# HIVE_SIGHT_NUCLEO.net
KiCad netlist of a schematic drawn in Altium Designer
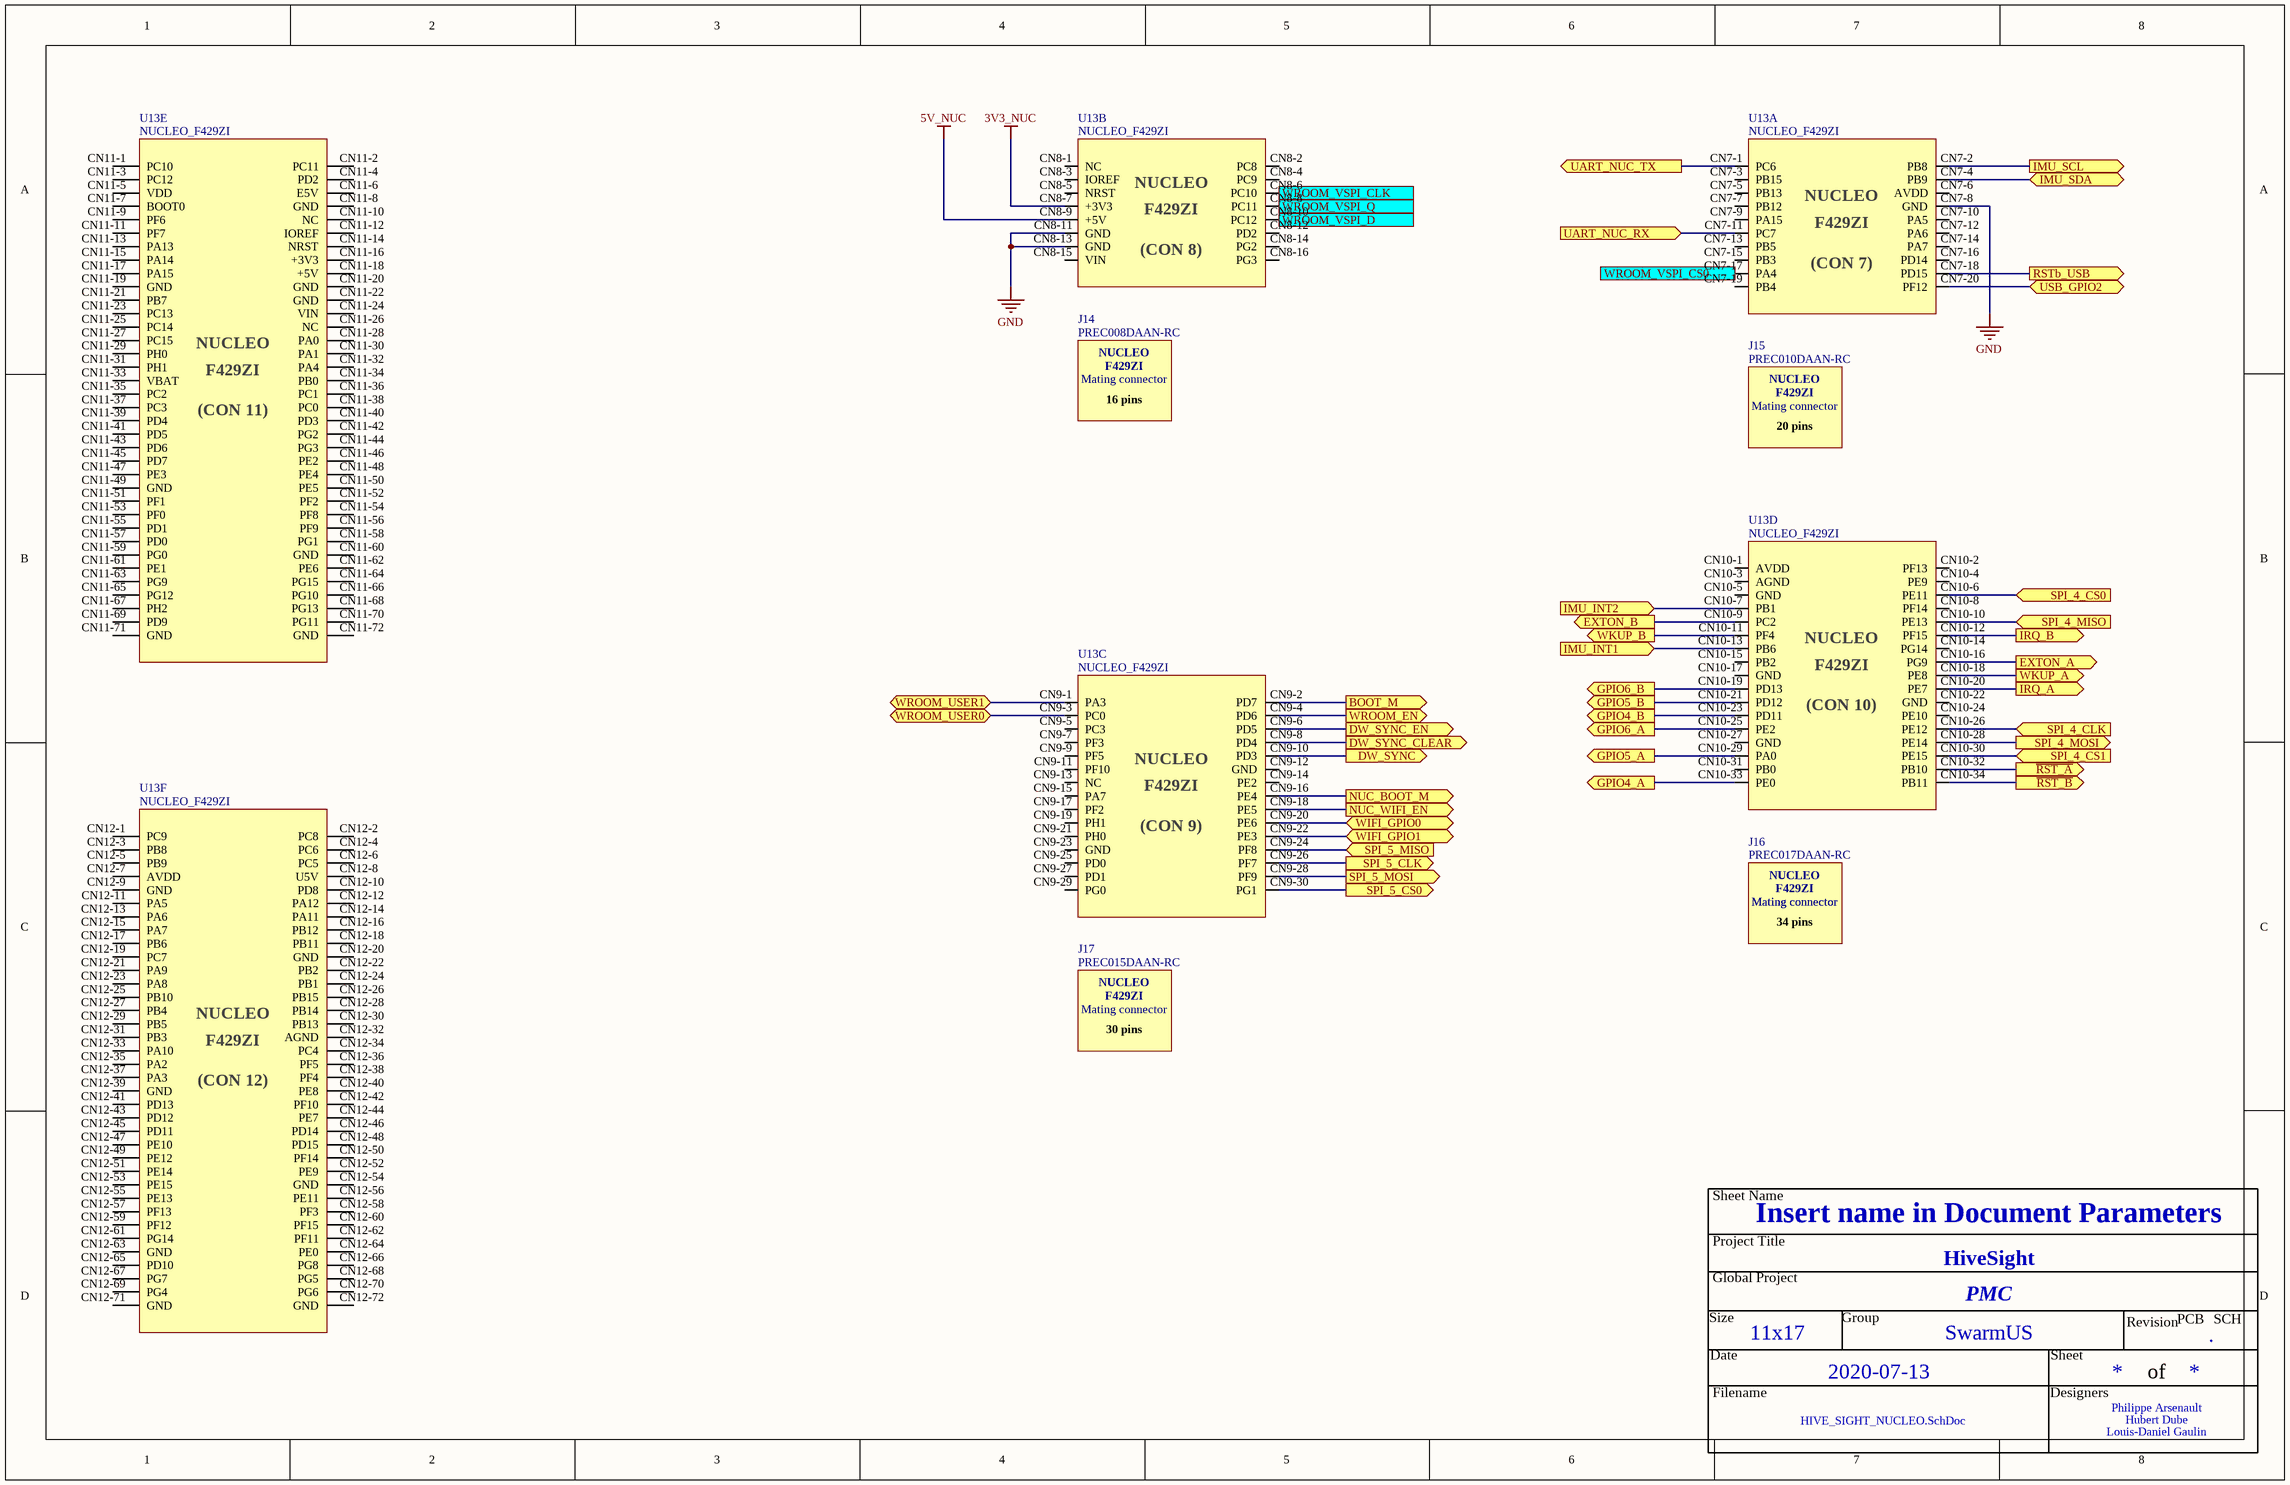
[diagram p0: HIVE_SIGHT_NUCLEO.SchDoc]

(export (version "E")
  (design (tool "Eeschema 10.0.6"))
  (components
    (comp (ref "J14")
      (value "PREC008DAAN-RC")
      (footprint "CON_HDR_NUCLEO_F429ZI_C008DAAN-RC")
      (description "CON - Header 16 positions 2x8  0.100\" - TH")
      (fields (field (name "CREATEDBY/DATE") "Louis-Daniel Gaulin / 21-10-2020"))
      (libsource (lib "SWARMUS_LIB") (part "CON_HDR_NUCLEO_F429ZI_PREC008DAAN-RC"))
    )
    (comp (ref "J15")
      (value "PREC010DAAN-RC")
      (footprint "CON_HDR_NUCLEO_F429ZI_C010DAAN-RC")
      (description "CON - Header 20 positions 2x10  0.100\" - TH")
      (fields (field (name "CREATEDBY/DATE") "Louis-Daniel Gaulin / 21-10-2020"))
      (libsource (lib "SWARMUS_LIB") (part "CON_HDR_NUCLEO_F429ZI_PREC010DAAN-RC"))
    )
    (comp (ref "J16")
      (value "PREC017DAAN-RC")
      (footprint "CON_HDR_NUCLEO_F429ZI_C017DAAN-RC")
      (description "CON - Header 34 positions 2x17  0.100\" - TH")
      (fields (field (name "CREATEDBY/DATE") "Louis-Daniel Gaulin / 21-10-2020"))
      (libsource (lib "SWARMUS_LIB") (part "CON_HDR_NUCLEO_F429ZI_PREC017DAAN-RC"))
    )
    (comp (ref "J17")
      (value "PREC015DAAN-RC")
      (footprint "CON_HDR_NUCLEO_F429ZI_C015DAAN-RC")
      (description "CON - Header 30 positions 2x15  0.100\" - TH")
      (fields (field (name "CREATEDBY/DATE") "Louis-Daniel Gaulin / 21-10-2020"))
      (libsource (lib "SWARMUS_LIB") (part "CON_HDR_NUCLEO_F429ZI_PREC015DAAN-RC"))
    )
    (comp (ref "U13")
      (value "NUCLEO_F429ZI")
      (footprint "MOD_NUCLEO-F429ZI")
      (description "MOD - F429ZI MCU Nucleo development board - MOD")
      (fields (field (name "CREATEDBY/DATE") "Louis-Daniel Gaulin"))
      (libsource (lib "SWARMUS_LIB") (part "MOD_NUCLEO_F429ZI"))
    )
  )
  (nets
    (net (code "1") (name "/BOOT_M") (class "Default")
      (node (ref "U13") (pin "CN9-2") (pinfunction "PD7_CN9-2") (pintype "passive"))
    )
    (net (code "2") (name "/DW_SYNC") (class "Default")
      (node (ref "U13") (pin "CN9-10") (pinfunction "PD3_CN9-10") (pintype "passive"))
    )
    (net (code "3") (name "/DW_SYNC_CLEAR") (class "Default")
      (node (ref "U13") (pin "CN9-8") (pinfunction "PD4_CN9-8") (pintype "passive"))
    )
    (net (code "4") (name "/DW_SYNC_EN") (class "Default")
      (node (ref "U13") (pin "CN9-6") (pinfunction "PD5_CN9-6") (pintype "passive"))
    )
    (net (code "5") (name "/EXTON_A") (class "Default")
      (node (ref "U13") (pin "CN10-16") (pinfunction "PG9_CN10-16") (pintype "passive"))
    )
    (net (code "6") (name "/EXTON_B") (class "Default")
      (node (ref "U13") (pin "CN10-9") (pinfunction "PC2_CN10-9") (pintype "passive"))
    )
    (net (code "7") (name "/GPIO4_A") (class "Default")
      (node (ref "U13") (pin "CN10-33") (pinfunction "PE0_CN10-33") (pintype "passive"))
    )
    (net (code "8") (name "/GPIO4_B") (class "Default")
      (node (ref "U13") (pin "CN10-23") (pinfunction "PD11_CN10-23") (pintype "passive"))
    )
    (net (code "9") (name "/GPIO5_A") (class "Default")
      (node (ref "U13") (pin "CN10-29") (pinfunction "PA0_CN10-29") (pintype "passive"))
    )
    (net (code "10") (name "/GPIO5_B") (class "Default")
      (node (ref "U13") (pin "CN10-21") (pinfunction "PD12_CN10-21") (pintype "passive"))
    )
    (net (code "11") (name "/GPIO6_A") (class "Default")
      (node (ref "U13") (pin "CN10-25") (pinfunction "PE2_CN10-25") (pintype "passive"))
    )
    (net (code "12") (name "/GPIO6_B") (class "Default")
      (node (ref "U13") (pin "CN10-19") (pinfunction "PD13_CN10-19") (pintype "passive"))
    )
    (net (code "13") (name "/IMU_INT1") (class "Default")
      (node (ref "U13") (pin "CN10-13") (pinfunction "PB6_CN10-13") (pintype "passive"))
    )
    (net (code "14") (name "/IMU_INT2") (class "Default")
      (node (ref "U13") (pin "CN10-7") (pinfunction "PB1_CN10-7") (pintype "passive"))
    )
    (net (code "15") (name "/IMU_SCL") (class "Default")
      (node (ref "U13") (pin "CN7-2") (pinfunction "PB8_CN7-2") (pintype "passive"))
    )
    (net (code "16") (name "/IMU_SDA") (class "Default")
      (node (ref "U13") (pin "CN7-4") (pinfunction "PB9_CN7-4") (pintype "passive"))
    )
    (net (code "17") (name "/IRQ_A") (class "Default")
      (node (ref "U13") (pin "CN10-20") (pinfunction "PE7_CN10-20") (pintype "passive"))
    )
    (net (code "18") (name "/IRQ_B") (class "Default")
      (node (ref "U13") (pin "CN10-12") (pinfunction "PF15_CN10-12") (pintype "passive"))
    )
    (net (code "19") (name "/NUC_BOOT_M") (class "Default")
      (node (ref "U13") (pin "CN9-16") (pinfunction "PE4_CN9-16") (pintype "passive"))
    )
    (net (code "20") (name "/NUC_WIFI_EN") (class "Default")
      (node (ref "U13") (pin "CN9-18") (pinfunction "PE5_CN9-18") (pintype "passive"))
    )
    (net (code "21") (name "/RST_A") (class "Default")
      (node (ref "U13") (pin "CN10-32") (pinfunction "PB10_CN10-32") (pintype "passive"))
    )
    (net (code "22") (name "/RST_B") (class "Default")
      (node (ref "U13") (pin "CN10-34") (pinfunction "PB11_CN10-34") (pintype "passive"))
    )
    (net (code "23") (name "/RSTb_USB") (class "Default")
      (node (ref "U13") (pin "CN7-18") (pinfunction "PD15_CN7-18") (pintype "passive"))
    )
    (net (code "24") (name "/SPI_4_CLK") (class "Default")
      (node (ref "U13") (pin "CN10-26") (pinfunction "PE12_CN10-26") (pintype "passive"))
    )
    (net (code "25") (name "/SPI_4_CS0") (class "Default")
      (node (ref "U13") (pin "CN10-6") (pinfunction "PE11_CN10-6") (pintype "passive"))
    )
    (net (code "26") (name "/SPI_4_CS1") (class "Default")
      (node (ref "U13") (pin "CN10-30") (pinfunction "PE15_CN10-30") (pintype "passive"))
    )
    (net (code "27") (name "/SPI_4_MISO") (class "Default")
      (node (ref "U13") (pin "CN10-10") (pinfunction "PE13_CN10-10") (pintype "passive"))
    )
    (net (code "28") (name "/SPI_4_MOSI") (class "Default")
      (node (ref "U13") (pin "CN10-28") (pinfunction "PE14_CN10-28") (pintype "passive"))
    )
    (net (code "29") (name "/SPI_5_CLK") (class "Default")
      (node (ref "U13") (pin "CN9-26") (pinfunction "PF7_CN9-26") (pintype "passive"))
    )
    (net (code "30") (name "/SPI_5_CS0") (class "Default")
      (node (ref "U13") (pin "CN9-30") (pinfunction "PG1_CN9-30") (pintype "passive"))
    )
    (net (code "31") (name "/SPI_5_MISO") (class "Default")
      (node (ref "U13") (pin "CN9-24") (pinfunction "PF8_CN9-24") (pintype "passive"))
    )
    (net (code "32") (name "/SPI_5_MOSI") (class "Default")
      (node (ref "U13") (pin "CN9-28") (pinfunction "PF9_CN9-28") (pintype "passive"))
    )
    (net (code "33") (name "/UART_NUC_RX") (class "Default")
      (node (ref "U13") (pin "CN7-11") (pinfunction "PC7_CN7-11") (pintype "passive"))
    )
    (net (code "34") (name "/UART_NUC_TX") (class "Default")
      (node (ref "U13") (pin "CN7-1") (pinfunction "PC6_CN7-1") (pintype "passive"))
    )
    (net (code "35") (name "/USB_GPIO2") (class "Default")
      (node (ref "U13") (pin "CN7-20") (pinfunction "PF12_CN7-20") (pintype "passive"))
    )
    (net (code "36") (name "/WIFI_GPIO0") (class "Default")
      (node (ref "U13") (pin "CN9-20") (pinfunction "PE6_CN9-20") (pintype "passive"))
    )
    (net (code "37") (name "/WIFI_GPIO1") (class "Default")
      (node (ref "U13") (pin "CN9-22") (pinfunction "PE3_CN9-22") (pintype "passive"))
    )
    (net (code "38") (name "/WKUP_A") (class "Default")
      (node (ref "U13") (pin "CN10-18") (pinfunction "PE8_CN10-18") (pintype "passive"))
    )
    (net (code "39") (name "/WKUP_B") (class "Default")
      (node (ref "U13") (pin "CN10-11") (pinfunction "PF4_CN10-11") (pintype "passive"))
    )
    (net (code "40") (name "/WROOM_EN") (class "Default")
      (node (ref "U13") (pin "CN9-4") (pinfunction "PD6_CN9-4") (pintype "passive"))
    )
    (net (code "41") (name "/WROOM_USER0") (class "Default")
      (node (ref "U13") (pin "CN9-3") (pinfunction "PC0_CN9-3") (pintype "passive"))
    )
    (net (code "42") (name "/WROOM_USER1") (class "Default")
      (node (ref "U13") (pin "CN9-1") (pinfunction "PA3_CN9-1") (pintype "passive"))
    )
    (net (code "43") (name "/WROOM_VSPI_CLK") (class "Default")
      (node (ref "U13") (pin "CN8-6") (pinfunction "PC10_CN8-6") (pintype "passive"))
    )
    (net (code "44") (name "/WROOM_VSPI_CS0") (class "Default")
      (node (ref "U13") (pin "CN7-17") (pinfunction "PA4_CN7-17") (pintype "passive"))
    )
    (net (code "45") (name "/WROOM_VSPI_D") (class "Default")
      (node (ref "U13") (pin "CN8-10") (pinfunction "PC12_CN8-10") (pintype "passive"))
    )
    (net (code "46") (name "/WROOM_VSPI_Q") (class "Default")
      (node (ref "U13") (pin "CN8-8") (pinfunction "PC11_CN8-8") (pintype "passive"))
    )
    (net (code "47") (name "3V3_NUC") (class "Default")
      (node (ref "U13") (pin "CN8-7") (pinfunction "+3V3_CN8-7") (pintype "passive"))
    )
    (net (code "48") (name "5V_NUC") (class "Default")
      (node (ref "U13") (pin "CN8-9") (pinfunction "+5V_CN8-9") (pintype "passive"))
    )
    (net (code "49") (name "GND") (class "Default")
      (node (ref "U13") (pin "CN7-8") (pinfunction "GND_CN7-8") (pintype "passive"))
      (node (ref "U13") (pin "CN8-11") (pinfunction "GND_CN8-11") (pintype "passive"))
      (node (ref "U13") (pin "CN8-13") (pinfunction "GND_CN8-13") (pintype "passive"))
    )
    (net (code "50") (name "unconnected-(U13A-AVDD-PadCN7-6)") (class "Default")
      (node (ref "U13") (pin "CN7-6") (pinfunction "AVDD_CN7-6") (pintype "passive"))
    )
    (net (code "51") (name "unconnected-(U13A-PA5-PadCN7-10)") (class "Default")
      (node (ref "U13") (pin "CN7-10") (pinfunction "PA5_CN7-10") (pintype "passive"))
    )
    (net (code "52") (name "unconnected-(U13A-PA6-PadCN7-12)") (class "Default")
      (node (ref "U13") (pin "CN7-12") (pinfunction "PA6_CN7-12") (pintype "passive"))
    )
    (net (code "53") (name "unconnected-(U13A-PA7-PadCN7-14)") (class "Default")
      (node (ref "U13") (pin "CN7-14") (pinfunction "PA7_CN7-14") (pintype "passive"))
    )
    (net (code "54") (name "unconnected-(U13A-PA15-PadCN7-9)") (class "Default")
      (node (ref "U13") (pin "CN7-9") (pinfunction "PA15_CN7-9") (pintype "passive"))
    )
    (net (code "55") (name "unconnected-(U13A-PB3-PadCN7-15)") (class "Default")
      (node (ref "U13") (pin "CN7-15") (pinfunction "PB3_CN7-15") (pintype "passive"))
    )
    (net (code "56") (name "unconnected-(U13A-PB4-PadCN7-19)") (class "Default")
      (node (ref "U13") (pin "CN7-19") (pinfunction "PB4_CN7-19") (pintype "passive"))
    )
    (net (code "57") (name "unconnected-(U13A-PB5-PadCN7-13)") (class "Default")
      (node (ref "U13") (pin "CN7-13") (pinfunction "PB5_CN7-13") (pintype "passive"))
    )
    (net (code "58") (name "unconnected-(U13A-PB12-PadCN7-7)") (class "Default")
      (node (ref "U13") (pin "CN7-7") (pinfunction "PB12_CN7-7") (pintype "passive"))
    )
    (net (code "59") (name "unconnected-(U13A-PB13-PadCN7-5)") (class "Default")
      (node (ref "U13") (pin "CN7-5") (pinfunction "PB13_CN7-5") (pintype "passive"))
    )
    (net (code "60") (name "unconnected-(U13A-PB15-PadCN7-3)") (class "Default")
      (node (ref "U13") (pin "CN7-3") (pinfunction "PB15_CN7-3") (pintype "passive"))
    )
    (net (code "61") (name "unconnected-(U13A-PD14-PadCN7-16)") (class "Default")
      (node (ref "U13") (pin "CN7-16") (pinfunction "PD14_CN7-16") (pintype "passive"))
    )
    (net (code "62") (name "unconnected-(U13B-IOREF-PadCN8-3)") (class "Default")
      (node (ref "U13") (pin "CN8-3") (pinfunction "IOREF_CN8-3") (pintype "passive"))
    )
    (net (code "63") (name "unconnected-(U13B-NC-PadCN8-1)") (class "Default")
      (node (ref "U13") (pin "CN8-1") (pinfunction "NC_CN8-1") (pintype "passive"))
    )
    (net (code "64") (name "unconnected-(U13B-NRST-PadCN8-5)") (class "Default")
      (node (ref "U13") (pin "CN8-5") (pinfunction "NRST_CN8-5") (pintype "passive"))
    )
    (net (code "65") (name "unconnected-(U13B-PC8-PadCN8-2)") (class "Default")
      (node (ref "U13") (pin "CN8-2") (pinfunction "PC8_CN8-2") (pintype "passive"))
    )
    (net (code "66") (name "unconnected-(U13B-PC9-PadCN8-4)") (class "Default")
      (node (ref "U13") (pin "CN8-4") (pinfunction "PC9_CN8-4") (pintype "passive"))
    )
    (net (code "67") (name "unconnected-(U13B-PD2-PadCN8-12)") (class "Default")
      (node (ref "U13") (pin "CN8-12") (pinfunction "PD2_CN8-12") (pintype "passive"))
    )
    (net (code "68") (name "unconnected-(U13B-PG2-PadCN8-14)") (class "Default")
      (node (ref "U13") (pin "CN8-14") (pinfunction "PG2_CN8-14") (pintype "passive"))
    )
    (net (code "69") (name "unconnected-(U13B-PG3-PadCN8-16)") (class "Default")
      (node (ref "U13") (pin "CN8-16") (pinfunction "PG3_CN8-16") (pintype "passive"))
    )
    (net (code "70") (name "unconnected-(U13B-VIN-PadCN8-15)") (class "Default")
      (node (ref "U13") (pin "CN8-15") (pinfunction "VIN_CN8-15") (pintype "passive"))
    )
    (net (code "71") (name "unconnected-(U13C-GND-PadCN9-12)") (class "Default")
      (node (ref "U13") (pin "CN9-12") (pinfunction "GND_CN9-12") (pintype "passive"))
    )
    (net (code "72") (name "unconnected-(U13C-GND-PadCN9-23)") (class "Default")
      (node (ref "U13") (pin "CN9-23") (pinfunction "GND_CN9-23") (pintype "passive"))
    )
    (net (code "73") (name "unconnected-(U13C-NC-PadCN9-13)") (class "Default")
      (node (ref "U13") (pin "CN9-13") (pinfunction "NC_CN9-13") (pintype "passive"))
    )
    (net (code "74") (name "unconnected-(U13C-PA7-PadCN9-15)") (class "Default")
      (node (ref "U13") (pin "CN9-15") (pinfunction "PA7_CN9-15") (pintype "passive"))
    )
    (net (code "75") (name "unconnected-(U13C-PC3-PadCN9-5)") (class "Default")
      (node (ref "U13") (pin "CN9-5") (pinfunction "PC3_CN9-5") (pintype "passive"))
    )
    (net (code "76") (name "unconnected-(U13C-PD0-PadCN9-25)") (class "Default")
      (node (ref "U13") (pin "CN9-25") (pinfunction "PD0_CN9-25") (pintype "passive"))
    )
    (net (code "77") (name "unconnected-(U13C-PD1-PadCN9-27)") (class "Default")
      (node (ref "U13") (pin "CN9-27") (pinfunction "PD1_CN9-27") (pintype "passive"))
    )
    (net (code "78") (name "unconnected-(U13C-PE2-PadCN9-14)") (class "Default")
      (node (ref "U13") (pin "CN9-14") (pinfunction "PE2_CN9-14") (pintype "passive"))
    )
    (net (code "79") (name "unconnected-(U13C-PF2-PadCN9-17)") (class "Default")
      (node (ref "U13") (pin "CN9-17") (pinfunction "PF2_CN9-17") (pintype "passive"))
    )
    (net (code "80") (name "unconnected-(U13C-PF3-PadCN9-7)") (class "Default")
      (node (ref "U13") (pin "CN9-7") (pinfunction "PF3_CN9-7") (pintype "passive"))
    )
    (net (code "81") (name "unconnected-(U13C-PF5-PadCN9-9)") (class "Default")
      (node (ref "U13") (pin "CN9-9") (pinfunction "PF5_CN9-9") (pintype "passive"))
    )
    (net (code "82") (name "unconnected-(U13C-PF10-PadCN9-11)") (class "Default")
      (node (ref "U13") (pin "CN9-11") (pinfunction "PF10_CN9-11") (pintype "passive"))
    )
    (net (code "83") (name "unconnected-(U13C-PG0-PadCN9-29)") (class "Default")
      (node (ref "U13") (pin "CN9-29") (pinfunction "PG0_CN9-29") (pintype "passive"))
    )
    (net (code "84") (name "unconnected-(U13C-PH0-PadCN9-21)") (class "Default")
      (node (ref "U13") (pin "CN9-21") (pinfunction "PH0_CN9-21") (pintype "passive"))
    )
    (net (code "85") (name "unconnected-(U13C-PH1-PadCN9-19)") (class "Default")
      (node (ref "U13") (pin "CN9-19") (pinfunction "PH1_CN9-19") (pintype "passive"))
    )
    (net (code "86") (name "unconnected-(U13D-AGND-PadCN10-3)") (class "Default")
      (node (ref "U13") (pin "CN10-3") (pinfunction "AGND_CN10-3") (pintype "passive"))
    )
    (net (code "87") (name "unconnected-(U13D-AVDD-PadCN10-1)") (class "Default")
      (node (ref "U13") (pin "CN10-1") (pinfunction "AVDD_CN10-1") (pintype "passive"))
    )
    (net (code "88") (name "unconnected-(U13D-GND-PadCN10-5)") (class "Default")
      (node (ref "U13") (pin "CN10-5") (pinfunction "GND_CN10-5") (pintype "passive"))
    )
    (net (code "89") (name "unconnected-(U13D-GND-PadCN10-17)") (class "Default")
      (node (ref "U13") (pin "CN10-17") (pinfunction "GND_CN10-17") (pintype "passive"))
    )
    (net (code "90") (name "unconnected-(U13D-GND-PadCN10-22)") (class "Default")
      (node (ref "U13") (pin "CN10-22") (pinfunction "GND_CN10-22") (pintype "passive"))
    )
    (net (code "91") (name "unconnected-(U13D-GND-PadCN10-27)") (class "Default")
      (node (ref "U13") (pin "CN10-27") (pinfunction "GND_CN10-27") (pintype "passive"))
    )
    (net (code "92") (name "unconnected-(U13D-PB0-PadCN10-31)") (class "Default")
      (node (ref "U13") (pin "CN10-31") (pinfunction "PB0_CN10-31") (pintype "passive"))
    )
    (net (code "93") (name "unconnected-(U13D-PB2-PadCN10-15)") (class "Default")
      (node (ref "U13") (pin "CN10-15") (pinfunction "PB2_CN10-15") (pintype "passive"))
    )
    (net (code "94") (name "unconnected-(U13D-PE9-PadCN10-4)") (class "Default")
      (node (ref "U13") (pin "CN10-4") (pinfunction "PE9_CN10-4") (pintype "passive"))
    )
    (net (code "95") (name "unconnected-(U13D-PE10-PadCN10-24)") (class "Default")
      (node (ref "U13") (pin "CN10-24") (pinfunction "PE10_CN10-24") (pintype "passive"))
    )
    (net (code "96") (name "unconnected-(U13D-PF13-PadCN10-2)") (class "Default")
      (node (ref "U13") (pin "CN10-2") (pinfunction "PF13_CN10-2") (pintype "passive"))
    )
    (net (code "97") (name "unconnected-(U13D-PF14-PadCN10-8)") (class "Default")
      (node (ref "U13") (pin "CN10-8") (pinfunction "PF14_CN10-8") (pintype "passive"))
    )
    (net (code "98") (name "unconnected-(U13D-PG14-PadCN10-14)") (class "Default")
      (node (ref "U13") (pin "CN10-14") (pinfunction "PG14_CN10-14") (pintype "passive"))
    )
    (net (code "99") (name "unconnected-(U13E-+3V3-PadCN11-16)") (class "Default")
      (node (ref "U13") (pin "CN11-16") (pinfunction "+3V3_CN11-16") (pintype "passive"))
    )
    (net (code "100") (name "unconnected-(U13E-+5V-PadCN11-18)") (class "Default")
      (node (ref "U13") (pin "CN11-18") (pinfunction "+5V_CN11-18") (pintype "passive"))
    )
    (net (code "101") (name "unconnected-(U13E-BOOT0-PadCN11-7)") (class "Default")
      (node (ref "U13") (pin "CN11-7") (pinfunction "BOOT0_CN11-7") (pintype "passive"))
    )
    (net (code "102") (name "unconnected-(U13E-E5V-PadCN11-6)") (class "Default")
      (node (ref "U13") (pin "CN11-6") (pinfunction "E5V_CN11-6") (pintype "passive"))
    )
    (net (code "103") (name "unconnected-(U13E-GND-PadCN11-8)") (class "Default")
      (node (ref "U13") (pin "CN11-8") (pinfunction "GND_CN11-8") (pintype "passive"))
    )
    (net (code "104") (name "unconnected-(U13E-GND-PadCN11-19)") (class "Default")
      (node (ref "U13") (pin "CN11-19") (pinfunction "GND_CN11-19") (pintype "passive"))
    )
    (net (code "105") (name "unconnected-(U13E-GND-PadCN11-20)") (class "Default")
      (node (ref "U13") (pin "CN11-20") (pinfunction "GND_CN11-20") (pintype "passive"))
    )
    (net (code "106") (name "unconnected-(U13E-GND-PadCN11-22)") (class "Default")
      (node (ref "U13") (pin "CN11-22") (pinfunction "GND_CN11-22") (pintype "passive"))
    )
    (net (code "107") (name "unconnected-(U13E-GND-PadCN11-49)") (class "Default")
      (node (ref "U13") (pin "CN11-49") (pinfunction "GND_CN11-49") (pintype "passive"))
    )
    (net (code "108") (name "unconnected-(U13E-GND-PadCN11-60)") (class "Default")
      (node (ref "U13") (pin "CN11-60") (pinfunction "GND_CN11-60") (pintype "passive"))
    )
    (net (code "109") (name "unconnected-(U13E-GND-PadCN11-71)") (class "Default")
      (node (ref "U13") (pin "CN11-71") (pinfunction "GND_CN11-71") (pintype "passive"))
    )
    (net (code "110") (name "unconnected-(U13E-GND-PadCN11-72)") (class "Default")
      (node (ref "U13") (pin "CN11-72") (pinfunction "GND_CN11-72") (pintype "passive"))
    )
    (net (code "111") (name "unconnected-(U13E-IOREF-PadCN11-12)") (class "Default")
      (node (ref "U13") (pin "CN11-12") (pinfunction "IOREF_CN11-12") (pintype "passive"))
    )
    (net (code "112") (name "unconnected-(U13E-NC-PadCN11-10)") (class "Default")
      (node (ref "U13") (pin "CN11-10") (pinfunction "NC_CN11-10") (pintype "passive"))
    )
    (net (code "113") (name "unconnected-(U13E-NC-PadCN11-26)") (class "Default")
      (node (ref "U13") (pin "CN11-26") (pinfunction "NC_CN11-26") (pintype "passive"))
    )
    (net (code "114") (name "unconnected-(U13E-NRST-PadCN11-14)") (class "Default")
      (node (ref "U13") (pin "CN11-14") (pinfunction "NRST_CN11-14") (pintype "passive"))
    )
    (net (code "115") (name "unconnected-(U13E-PA0-PadCN11-28)") (class "Default")
      (node (ref "U13") (pin "CN11-28") (pinfunction "PA0_CN11-28") (pintype "passive"))
    )
    (net (code "116") (name "unconnected-(U13E-PA1-PadCN11-30)") (class "Default")
      (node (ref "U13") (pin "CN11-30") (pinfunction "PA1_CN11-30") (pintype "passive"))
    )
    (net (code "117") (name "unconnected-(U13E-PA4-PadCN11-32)") (class "Default")
      (node (ref "U13") (pin "CN11-32") (pinfunction "PA4_CN11-32") (pintype "passive"))
    )
    (net (code "118") (name "unconnected-(U13E-PA13-PadCN11-13)") (class "Default")
      (node (ref "U13") (pin "CN11-13") (pinfunction "PA13_CN11-13") (pintype "passive"))
    )
    (net (code "119") (name "unconnected-(U13E-PA14-PadCN11-15)") (class "Default")
      (node (ref "U13") (pin "CN11-15") (pinfunction "PA14_CN11-15") (pintype "passive"))
    )
    (net (code "120") (name "unconnected-(U13E-PA15-PadCN11-17)") (class "Default")
      (node (ref "U13") (pin "CN11-17") (pinfunction "PA15_CN11-17") (pintype "passive"))
    )
    (net (code "121") (name "unconnected-(U13E-PB0-PadCN11-34)") (class "Default")
      (node (ref "U13") (pin "CN11-34") (pinfunction "PB0_CN11-34") (pintype "passive"))
    )
    (net (code "122") (name "unconnected-(U13E-PB7-PadCN11-21)") (class "Default")
      (node (ref "U13") (pin "CN11-21") (pinfunction "PB7_CN11-21") (pintype "passive"))
    )
    (net (code "123") (name "unconnected-(U13E-PC0-PadCN11-38)") (class "Default")
      (node (ref "U13") (pin "CN11-38") (pinfunction "PC0_CN11-38") (pintype "passive"))
    )
    (net (code "124") (name "unconnected-(U13E-PC1-PadCN11-36)") (class "Default")
      (node (ref "U13") (pin "CN11-36") (pinfunction "PC1_CN11-36") (pintype "passive"))
    )
    (net (code "125") (name "unconnected-(U13E-PC2-PadCN11-35)") (class "Default")
      (node (ref "U13") (pin "CN11-35") (pinfunction "PC2_CN11-35") (pintype "passive"))
    )
    (net (code "126") (name "unconnected-(U13E-PC3-PadCN11-37)") (class "Default")
      (node (ref "U13") (pin "CN11-37") (pinfunction "PC3_CN11-37") (pintype "passive"))
    )
    (net (code "127") (name "unconnected-(U13E-PC10-PadCN11-1)") (class "Default")
      (node (ref "U13") (pin "CN11-1") (pinfunction "PC10_CN11-1") (pintype "passive"))
    )
    (net (code "128") (name "unconnected-(U13E-PC11-PadCN11-2)") (class "Default")
      (node (ref "U13") (pin "CN11-2") (pinfunction "PC11_CN11-2") (pintype "passive"))
    )
    (net (code "129") (name "unconnected-(U13E-PC12-PadCN11-3)") (class "Default")
      (node (ref "U13") (pin "CN11-3") (pinfunction "PC12_CN11-3") (pintype "passive"))
    )
    (net (code "130") (name "unconnected-(U13E-PC13-PadCN11-23)") (class "Default")
      (node (ref "U13") (pin "CN11-23") (pinfunction "PC13_CN11-23") (pintype "passive"))
    )
    (net (code "131") (name "unconnected-(U13E-PC14-PadCN11-25)") (class "Default")
      (node (ref "U13") (pin "CN11-25") (pinfunction "PC14_CN11-25") (pintype "passive"))
    )
    (net (code "132") (name "unconnected-(U13E-PC15-PadCN11-27)") (class "Default")
      (node (ref "U13") (pin "CN11-27") (pinfunction "PC15_CN11-27") (pintype "passive"))
    )
    (net (code "133") (name "unconnected-(U13E-PD0-PadCN11-57)") (class "Default")
      (node (ref "U13") (pin "CN11-57") (pinfunction "PD0_CN11-57") (pintype "passive"))
    )
    (net (code "134") (name "unconnected-(U13E-PD1-PadCN11-55)") (class "Default")
      (node (ref "U13") (pin "CN11-55") (pinfunction "PD1_CN11-55") (pintype "passive"))
    )
    (net (code "135") (name "unconnected-(U13E-PD2-PadCN11-4)") (class "Default")
      (node (ref "U13") (pin "CN11-4") (pinfunction "PD2_CN11-4") (pintype "passive"))
    )
    (net (code "136") (name "unconnected-(U13E-PD3-PadCN11-40)") (class "Default")
      (node (ref "U13") (pin "CN11-40") (pinfunction "PD3_CN11-40") (pintype "passive"))
    )
    (net (code "137") (name "unconnected-(U13E-PD4-PadCN11-39)") (class "Default")
      (node (ref "U13") (pin "CN11-39") (pinfunction "PD4_CN11-39") (pintype "passive"))
    )
    (net (code "138") (name "unconnected-(U13E-PD5-PadCN11-41)") (class "Default")
      (node (ref "U13") (pin "CN11-41") (pinfunction "PD5_CN11-41") (pintype "passive"))
    )
    (net (code "139") (name "unconnected-(U13E-PD6-PadCN11-43)") (class "Default")
      (node (ref "U13") (pin "CN11-43") (pinfunction "PD6_CN11-43") (pintype "passive"))
    )
    (net (code "140") (name "unconnected-(U13E-PD7-PadCN11-45)") (class "Default")
      (node (ref "U13") (pin "CN11-45") (pinfunction "PD7_CN11-45") (pintype "passive"))
    )
    (net (code "141") (name "unconnected-(U13E-PD9-PadCN11-69)") (class "Default")
      (node (ref "U13") (pin "CN11-69") (pinfunction "PD9_CN11-69") (pintype "passive"))
    )
    (net (code "142") (name "unconnected-(U13E-PE1-PadCN11-61)") (class "Default")
      (node (ref "U13") (pin "CN11-61") (pinfunction "PE1_CN11-61") (pintype "passive"))
    )
    (net (code "143") (name "unconnected-(U13E-PE2-PadCN11-46)") (class "Default")
      (node (ref "U13") (pin "CN11-46") (pinfunction "PE2_CN11-46") (pintype "passive"))
    )
    (net (code "144") (name "unconnected-(U13E-PE3-PadCN11-47)") (class "Default")
      (node (ref "U13") (pin "CN11-47") (pinfunction "PE3_CN11-47") (pintype "passive"))
    )
    (net (code "145") (name "unconnected-(U13E-PE4-PadCN11-48)") (class "Default")
      (node (ref "U13") (pin "CN11-48") (pinfunction "PE4_CN11-48") (pintype "passive"))
    )
    (net (code "146") (name "unconnected-(U13E-PE5-PadCN11-50)") (class "Default")
      (node (ref "U13") (pin "CN11-50") (pinfunction "PE5_CN11-50") (pintype "passive"))
    )
    (net (code "147") (name "unconnected-(U13E-PE6-PadCN11-62)") (class "Default")
      (node (ref "U13") (pin "CN11-62") (pinfunction "PE6_CN11-62") (pintype "passive"))
    )
    (net (code "148") (name "unconnected-(U13E-PF0-PadCN11-53)") (class "Default")
      (node (ref "U13") (pin "CN11-53") (pinfunction "PF0_CN11-53") (pintype "passive"))
    )
    (net (code "149") (name "unconnected-(U13E-PF1-PadCN11-51)") (class "Default")
      (node (ref "U13") (pin "CN11-51") (pinfunction "PF1_CN11-51") (pintype "passive"))
    )
    (net (code "150") (name "unconnected-(U13E-PF2-PadCN11-52)") (class "Default")
      (node (ref "U13") (pin "CN11-52") (pinfunction "PF2_CN11-52") (pintype "passive"))
    )
    (net (code "151") (name "unconnected-(U13E-PF6-PadCN11-9)") (class "Default")
      (node (ref "U13") (pin "CN11-9") (pinfunction "PF6_CN11-9") (pintype "passive"))
    )
    (net (code "152") (name "unconnected-(U13E-PF7-PadCN11-11)") (class "Default")
      (node (ref "U13") (pin "CN11-11") (pinfunction "PF7_CN11-11") (pintype "passive"))
    )
    (net (code "153") (name "unconnected-(U13E-PF8-PadCN11-54)") (class "Default")
      (node (ref "U13") (pin "CN11-54") (pinfunction "PF8_CN11-54") (pintype "passive"))
    )
    (net (code "154") (name "unconnected-(U13E-PF9-PadCN11-56)") (class "Default")
      (node (ref "U13") (pin "CN11-56") (pinfunction "PF9_CN11-56") (pintype "passive"))
    )
    (net (code "155") (name "unconnected-(U13E-PG0-PadCN11-59)") (class "Default")
      (node (ref "U13") (pin "CN11-59") (pinfunction "PG0_CN11-59") (pintype "passive"))
    )
    (net (code "156") (name "unconnected-(U13E-PG1-PadCN11-58)") (class "Default")
      (node (ref "U13") (pin "CN11-58") (pinfunction "PG1_CN11-58") (pintype "passive"))
    )
    (net (code "157") (name "unconnected-(U13E-PG2-PadCN11-42)") (class "Default")
      (node (ref "U13") (pin "CN11-42") (pinfunction "PG2_CN11-42") (pintype "passive"))
    )
    (net (code "158") (name "unconnected-(U13E-PG3-PadCN11-44)") (class "Default")
      (node (ref "U13") (pin "CN11-44") (pinfunction "PG3_CN11-44") (pintype "passive"))
    )
    (net (code "159") (name "unconnected-(U13E-PG9-PadCN11-63)") (class "Default")
      (node (ref "U13") (pin "CN11-63") (pinfunction "PG9_CN11-63") (pintype "passive"))
    )
    (net (code "160") (name "unconnected-(U13E-PG10-PadCN11-66)") (class "Default")
      (node (ref "U13") (pin "CN11-66") (pinfunction "PG10_CN11-66") (pintype "passive"))
    )
    (net (code "161") (name "unconnected-(U13E-PG11-PadCN11-70)") (class "Default")
      (node (ref "U13") (pin "CN11-70") (pinfunction "PG11_CN11-70") (pintype "passive"))
    )
    (net (code "162") (name "unconnected-(U13E-PG12-PadCN11-65)") (class "Default")
      (node (ref "U13") (pin "CN11-65") (pinfunction "PG12_CN11-65") (pintype "passive"))
    )
    (net (code "163") (name "unconnected-(U13E-PG13-PadCN11-68)") (class "Default")
      (node (ref "U13") (pin "CN11-68") (pinfunction "PG13_CN11-68") (pintype "passive"))
    )
    (net (code "164") (name "unconnected-(U13E-PG15-PadCN11-64)") (class "Default")
      (node (ref "U13") (pin "CN11-64") (pinfunction "PG15_CN11-64") (pintype "passive"))
    )
    (net (code "165") (name "unconnected-(U13E-PH0-PadCN11-29)") (class "Default")
      (node (ref "U13") (pin "CN11-29") (pinfunction "PH0_CN11-29") (pintype "passive"))
    )
    (net (code "166") (name "unconnected-(U13E-PH1-PadCN11-31)") (class "Default")
      (node (ref "U13") (pin "CN11-31") (pinfunction "PH1_CN11-31") (pintype "passive"))
    )
    (net (code "167") (name "unconnected-(U13E-PH2-PadCN11-67)") (class "Default")
      (node (ref "U13") (pin "CN11-67") (pinfunction "PH2_CN11-67") (pintype "passive"))
    )
    (net (code "168") (name "unconnected-(U13E-VBAT-PadCN11-33)") (class "Default")
      (node (ref "U13") (pin "CN11-33") (pinfunction "VBAT_CN11-33") (pintype "passive"))
    )
    (net (code "169") (name "unconnected-(U13E-VDD-PadCN11-5)") (class "Default")
      (node (ref "U13") (pin "CN11-5") (pinfunction "VDD_CN11-5") (pintype "passive"))
    )
    (net (code "170") (name "unconnected-(U13E-VIN-PadCN11-24)") (class "Default")
      (node (ref "U13") (pin "CN11-24") (pinfunction "VIN_CN11-24") (pintype "passive"))
    )
    (net (code "171") (name "unconnected-(U13F-AGND-PadCN12-32)") (class "Default")
      (node (ref "U13") (pin "CN12-32") (pinfunction "AGND_CN12-32") (pintype "passive"))
    )
    (net (code "172") (name "unconnected-(U13F-AVDD-PadCN12-7)") (class "Default")
      (node (ref "U13") (pin "CN12-7") (pinfunction "AVDD_CN12-7") (pintype "passive"))
    )
    (net (code "173") (name "unconnected-(U13F-GND-PadCN12-9)") (class "Default")
      (node (ref "U13") (pin "CN12-9") (pinfunction "GND_CN12-9") (pintype "passive"))
    )
    (net (code "174") (name "unconnected-(U13F-GND-PadCN12-20)") (class "Default")
      (node (ref "U13") (pin "CN12-20") (pinfunction "GND_CN12-20") (pintype "passive"))
    )
    (net (code "175") (name "unconnected-(U13F-GND-PadCN12-39)") (class "Default")
      (node (ref "U13") (pin "CN12-39") (pinfunction "GND_CN12-39") (pintype "passive"))
    )
    (net (code "176") (name "unconnected-(U13F-GND-PadCN12-54)") (class "Default")
      (node (ref "U13") (pin "CN12-54") (pinfunction "GND_CN12-54") (pintype "passive"))
    )
    (net (code "177") (name "unconnected-(U13F-GND-PadCN12-63)") (class "Default")
      (node (ref "U13") (pin "CN12-63") (pinfunction "GND_CN12-63") (pintype "passive"))
    )
    (net (code "178") (name "unconnected-(U13F-GND-PadCN12-71)") (class "Default")
      (node (ref "U13") (pin "CN12-71") (pinfunction "GND_CN12-71") (pintype "passive"))
    )
    (net (code "179") (name "unconnected-(U13F-GND-PadCN12-72)") (class "Default")
      (node (ref "U13") (pin "CN12-72") (pinfunction "GND_CN12-72") (pintype "passive"))
    )
    (net (code "180") (name "unconnected-(U13F-PA2-PadCN12-35)") (class "Default")
      (node (ref "U13") (pin "CN12-35") (pinfunction "PA2_CN12-35") (pintype "passive"))
    )
    (net (code "181") (name "unconnected-(U13F-PA3-PadCN12-37)") (class "Default")
      (node (ref "U13") (pin "CN12-37") (pinfunction "PA3_CN12-37") (pintype "passive"))
    )
    (net (code "182") (name "unconnected-(U13F-PA5-PadCN12-11)") (class "Default")
      (node (ref "U13") (pin "CN12-11") (pinfunction "PA5_CN12-11") (pintype "passive"))
    )
    (net (code "183") (name "unconnected-(U13F-PA6-PadCN12-13)") (class "Default")
      (node (ref "U13") (pin "CN12-13") (pinfunction "PA6_CN12-13") (pintype "passive"))
    )
    (net (code "184") (name "unconnected-(U13F-PA7-PadCN12-15)") (class "Default")
      (node (ref "U13") (pin "CN12-15") (pinfunction "PA7_CN12-15") (pintype "passive"))
    )
    (net (code "185") (name "unconnected-(U13F-PA8-PadCN12-23)") (class "Default")
      (node (ref "U13") (pin "CN12-23") (pinfunction "PA8_CN12-23") (pintype "passive"))
    )
    (net (code "186") (name "unconnected-(U13F-PA9-PadCN12-21)") (class "Default")
      (node (ref "U13") (pin "CN12-21") (pinfunction "PA9_CN12-21") (pintype "passive"))
    )
    (net (code "187") (name "unconnected-(U13F-PA10-PadCN12-33)") (class "Default")
      (node (ref "U13") (pin "CN12-33") (pinfunction "PA10_CN12-33") (pintype "passive"))
    )
    (net (code "188") (name "unconnected-(U13F-PA11-PadCN12-14)") (class "Default")
      (node (ref "U13") (pin "CN12-14") (pinfunction "PA11_CN12-14") (pintype "passive"))
    )
    (net (code "189") (name "unconnected-(U13F-PA12-PadCN12-12)") (class "Default")
      (node (ref "U13") (pin "CN12-12") (pinfunction "PA12_CN12-12") (pintype "passive"))
    )
    (net (code "190") (name "unconnected-(U13F-PB1-PadCN12-24)") (class "Default")
      (node (ref "U13") (pin "CN12-24") (pinfunction "PB1_CN12-24") (pintype "passive"))
    )
    (net (code "191") (name "unconnected-(U13F-PB2-PadCN12-22)") (class "Default")
      (node (ref "U13") (pin "CN12-22") (pinfunction "PB2_CN12-22") (pintype "passive"))
    )
    (net (code "192") (name "unconnected-(U13F-PB3-PadCN12-31)") (class "Default")
      (node (ref "U13") (pin "CN12-31") (pinfunction "PB3_CN12-31") (pintype "passive"))
    )
    (net (code "193") (name "unconnected-(U13F-PB4-PadCN12-27)") (class "Default")
      (node (ref "U13") (pin "CN12-27") (pinfunction "PB4_CN12-27") (pintype "passive"))
    )
    (net (code "194") (name "unconnected-(U13F-PB5-PadCN12-29)") (class "Default")
      (node (ref "U13") (pin "CN12-29") (pinfunction "PB5_CN12-29") (pintype "passive"))
    )
    (net (code "195") (name "unconnected-(U13F-PB6-PadCN12-17)") (class "Default")
      (node (ref "U13") (pin "CN12-17") (pinfunction "PB6_CN12-17") (pintype "passive"))
    )
    (net (code "196") (name "unconnected-(U13F-PB8-PadCN12-3)") (class "Default")
      (node (ref "U13") (pin "CN12-3") (pinfunction "PB8_CN12-3") (pintype "passive"))
    )
    (net (code "197") (name "unconnected-(U13F-PB9-PadCN12-5)") (class "Default")
      (node (ref "U13") (pin "CN12-5") (pinfunction "PB9_CN12-5") (pintype "passive"))
    )
    (net (code "198") (name "unconnected-(U13F-PB10-PadCN12-25)") (class "Default")
      (node (ref "U13") (pin "CN12-25") (pinfunction "PB10_CN12-25") (pintype "passive"))
    )
    (net (code "199") (name "unconnected-(U13F-PB11-PadCN12-18)") (class "Default")
      (node (ref "U13") (pin "CN12-18") (pinfunction "PB11_CN12-18") (pintype "passive"))
    )
    (net (code "200") (name "unconnected-(U13F-PB12-PadCN12-16)") (class "Default")
      (node (ref "U13") (pin "CN12-16") (pinfunction "PB12_CN12-16") (pintype "passive"))
    )
    (net (code "201") (name "unconnected-(U13F-PB13-PadCN12-30)") (class "Default")
      (node (ref "U13") (pin "CN12-30") (pinfunction "PB13_CN12-30") (pintype "passive"))
    )
    (net (code "202") (name "unconnected-(U13F-PB14-PadCN12-28)") (class "Default")
      (node (ref "U13") (pin "CN12-28") (pinfunction "PB14_CN12-28") (pintype "passive"))
    )
    (net (code "203") (name "unconnected-(U13F-PB15-PadCN12-26)") (class "Default")
      (node (ref "U13") (pin "CN12-26") (pinfunction "PB15_CN12-26") (pintype "passive"))
    )
    (net (code "204") (name "unconnected-(U13F-PC4-PadCN12-34)") (class "Default")
      (node (ref "U13") (pin "CN12-34") (pinfunction "PC4_CN12-34") (pintype "passive"))
    )
    (net (code "205") (name "unconnected-(U13F-PC5-PadCN12-6)") (class "Default")
      (node (ref "U13") (pin "CN12-6") (pinfunction "PC5_CN12-6") (pintype "passive"))
    )
    (net (code "206") (name "unconnected-(U13F-PC6-PadCN12-4)") (class "Default")
      (node (ref "U13") (pin "CN12-4") (pinfunction "PC6_CN12-4") (pintype "passive"))
    )
    (net (code "207") (name "unconnected-(U13F-PC7-PadCN12-19)") (class "Default")
      (node (ref "U13") (pin "CN12-19") (pinfunction "PC7_CN12-19") (pintype "passive"))
    )
    (net (code "208") (name "unconnected-(U13F-PC8-PadCN12-2)") (class "Default")
      (node (ref "U13") (pin "CN12-2") (pinfunction "PC8_CN12-2") (pintype "passive"))
    )
    (net (code "209") (name "unconnected-(U13F-PC9-PadCN12-1)") (class "Default")
      (node (ref "U13") (pin "CN12-1") (pinfunction "PC9_CN12-1") (pintype "passive"))
    )
    (net (code "210") (name "unconnected-(U13F-PD8-PadCN12-10)") (class "Default")
      (node (ref "U13") (pin "CN12-10") (pinfunction "PD8_CN12-10") (pintype "passive"))
    )
    (net (code "211") (name "unconnected-(U13F-PD10-PadCN12-65)") (class "Default")
      (node (ref "U13") (pin "CN12-65") (pinfunction "PD10_CN12-65") (pintype "passive"))
    )
    (net (code "212") (name "unconnected-(U13F-PD11-PadCN12-45)") (class "Default")
      (node (ref "U13") (pin "CN12-45") (pinfunction "PD11_CN12-45") (pintype "passive"))
    )
    (net (code "213") (name "unconnected-(U13F-PD12-PadCN12-43)") (class "Default")
      (node (ref "U13") (pin "CN12-43") (pinfunction "PD12_CN12-43") (pintype "passive"))
    )
    (net (code "214") (name "unconnected-(U13F-PD13-PadCN12-41)") (class "Default")
      (node (ref "U13") (pin "CN12-41") (pinfunction "PD13_CN12-41") (pintype "passive"))
    )
    (net (code "215") (name "unconnected-(U13F-PD14-PadCN12-46)") (class "Default")
      (node (ref "U13") (pin "CN12-46") (pinfunction "PD14_CN12-46") (pintype "passive"))
    )
    (net (code "216") (name "unconnected-(U13F-PD15-PadCN12-48)") (class "Default")
      (node (ref "U13") (pin "CN12-48") (pinfunction "PD15_CN12-48") (pintype "passive"))
    )
    (net (code "217") (name "unconnected-(U13F-PE0-PadCN12-64)") (class "Default")
      (node (ref "U13") (pin "CN12-64") (pinfunction "PE0_CN12-64") (pintype "passive"))
    )
    (net (code "218") (name "unconnected-(U13F-PE7-PadCN12-44)") (class "Default")
      (node (ref "U13") (pin "CN12-44") (pinfunction "PE7_CN12-44") (pintype "passive"))
    )
    (net (code "219") (name "unconnected-(U13F-PE8-PadCN12-40)") (class "Default")
      (node (ref "U13") (pin "CN12-40") (pinfunction "PE8_CN12-40") (pintype "passive"))
    )
    (net (code "220") (name "unconnected-(U13F-PE9-PadCN12-52)") (class "Default")
      (node (ref "U13") (pin "CN12-52") (pinfunction "PE9_CN12-52") (pintype "passive"))
    )
    (net (code "221") (name "unconnected-(U13F-PE10-PadCN12-47)") (class "Default")
      (node (ref "U13") (pin "CN12-47") (pinfunction "PE10_CN12-47") (pintype "passive"))
    )
    (net (code "222") (name "unconnected-(U13F-PE11-PadCN12-56)") (class "Default")
      (node (ref "U13") (pin "CN12-56") (pinfunction "PE11_CN12-56") (pintype "passive"))
    )
    (net (code "223") (name "unconnected-(U13F-PE12-PadCN12-49)") (class "Default")
      (node (ref "U13") (pin "CN12-49") (pinfunction "PE12_CN12-49") (pintype "passive"))
    )
    (net (code "224") (name "unconnected-(U13F-PE13-PadCN12-55)") (class "Default")
      (node (ref "U13") (pin "CN12-55") (pinfunction "PE13_CN12-55") (pintype "passive"))
    )
    (net (code "225") (name "unconnected-(U13F-PE14-PadCN12-51)") (class "Default")
      (node (ref "U13") (pin "CN12-51") (pinfunction "PE14_CN12-51") (pintype "passive"))
    )
    (net (code "226") (name "unconnected-(U13F-PE15-PadCN12-53)") (class "Default")
      (node (ref "U13") (pin "CN12-53") (pinfunction "PE15_CN12-53") (pintype "passive"))
    )
    (net (code "227") (name "unconnected-(U13F-PF3-PadCN12-58)") (class "Default")
      (node (ref "U13") (pin "CN12-58") (pinfunction "PF3_CN12-58") (pintype "passive"))
    )
    (net (code "228") (name "unconnected-(U13F-PF4-PadCN12-38)") (class "Default")
      (node (ref "U13") (pin "CN12-38") (pinfunction "PF4_CN12-38") (pintype "passive"))
    )
    (net (code "229") (name "unconnected-(U13F-PF5-PadCN12-36)") (class "Default")
      (node (ref "U13") (pin "CN12-36") (pinfunction "PF5_CN12-36") (pintype "passive"))
    )
    (net (code "230") (name "unconnected-(U13F-PF10-PadCN12-42)") (class "Default")
      (node (ref "U13") (pin "CN12-42") (pinfunction "PF10_CN12-42") (pintype "passive"))
    )
    (net (code "231") (name "unconnected-(U13F-PF11-PadCN12-62)") (class "Default")
      (node (ref "U13") (pin "CN12-62") (pinfunction "PF11_CN12-62") (pintype "passive"))
    )
    (net (code "232") (name "unconnected-(U13F-PF12-PadCN12-59)") (class "Default")
      (node (ref "U13") (pin "CN12-59") (pinfunction "PF12_CN12-59") (pintype "passive"))
    )
    (net (code "233") (name "unconnected-(U13F-PF13-PadCN12-57)") (class "Default")
      (node (ref "U13") (pin "CN12-57") (pinfunction "PF13_CN12-57") (pintype "passive"))
    )
    (net (code "234") (name "unconnected-(U13F-PF14-PadCN12-50)") (class "Default")
      (node (ref "U13") (pin "CN12-50") (pinfunction "PF14_CN12-50") (pintype "passive"))
    )
    (net (code "235") (name "unconnected-(U13F-PF15-PadCN12-60)") (class "Default")
      (node (ref "U13") (pin "CN12-60") (pinfunction "PF15_CN12-60") (pintype "passive"))
    )
    (net (code "236") (name "unconnected-(U13F-PG4-PadCN12-69)") (class "Default")
      (node (ref "U13") (pin "CN12-69") (pinfunction "PG4_CN12-69") (pintype "passive"))
    )
    (net (code "237") (name "unconnected-(U13F-PG5-PadCN12-68)") (class "Default")
      (node (ref "U13") (pin "CN12-68") (pinfunction "PG5_CN12-68") (pintype "passive"))
    )
    (net (code "238") (name "unconnected-(U13F-PG6-PadCN12-70)") (class "Default")
      (node (ref "U13") (pin "CN12-70") (pinfunction "PG6_CN12-70") (pintype "passive"))
    )
    (net (code "239") (name "unconnected-(U13F-PG7-PadCN12-67)") (class "Default")
      (node (ref "U13") (pin "CN12-67") (pinfunction "PG7_CN12-67") (pintype "passive"))
    )
    (net (code "240") (name "unconnected-(U13F-PG8-PadCN12-66)") (class "Default")
      (node (ref "U13") (pin "CN12-66") (pinfunction "PG8_CN12-66") (pintype "passive"))
    )
    (net (code "241") (name "unconnected-(U13F-PG14-PadCN12-61)") (class "Default")
      (node (ref "U13") (pin "CN12-61") (pinfunction "PG14_CN12-61") (pintype "passive"))
    )
    (net (code "242") (name "unconnected-(U13F-U5V-PadCN12-8)") (class "Default")
      (node (ref "U13") (pin "CN12-8") (pinfunction "U5V_CN12-8") (pintype "passive"))
    )
  )
)
